# MotherBoard_Interconnect.net
KiCad netlist of a schematic drawn in Altium Designer
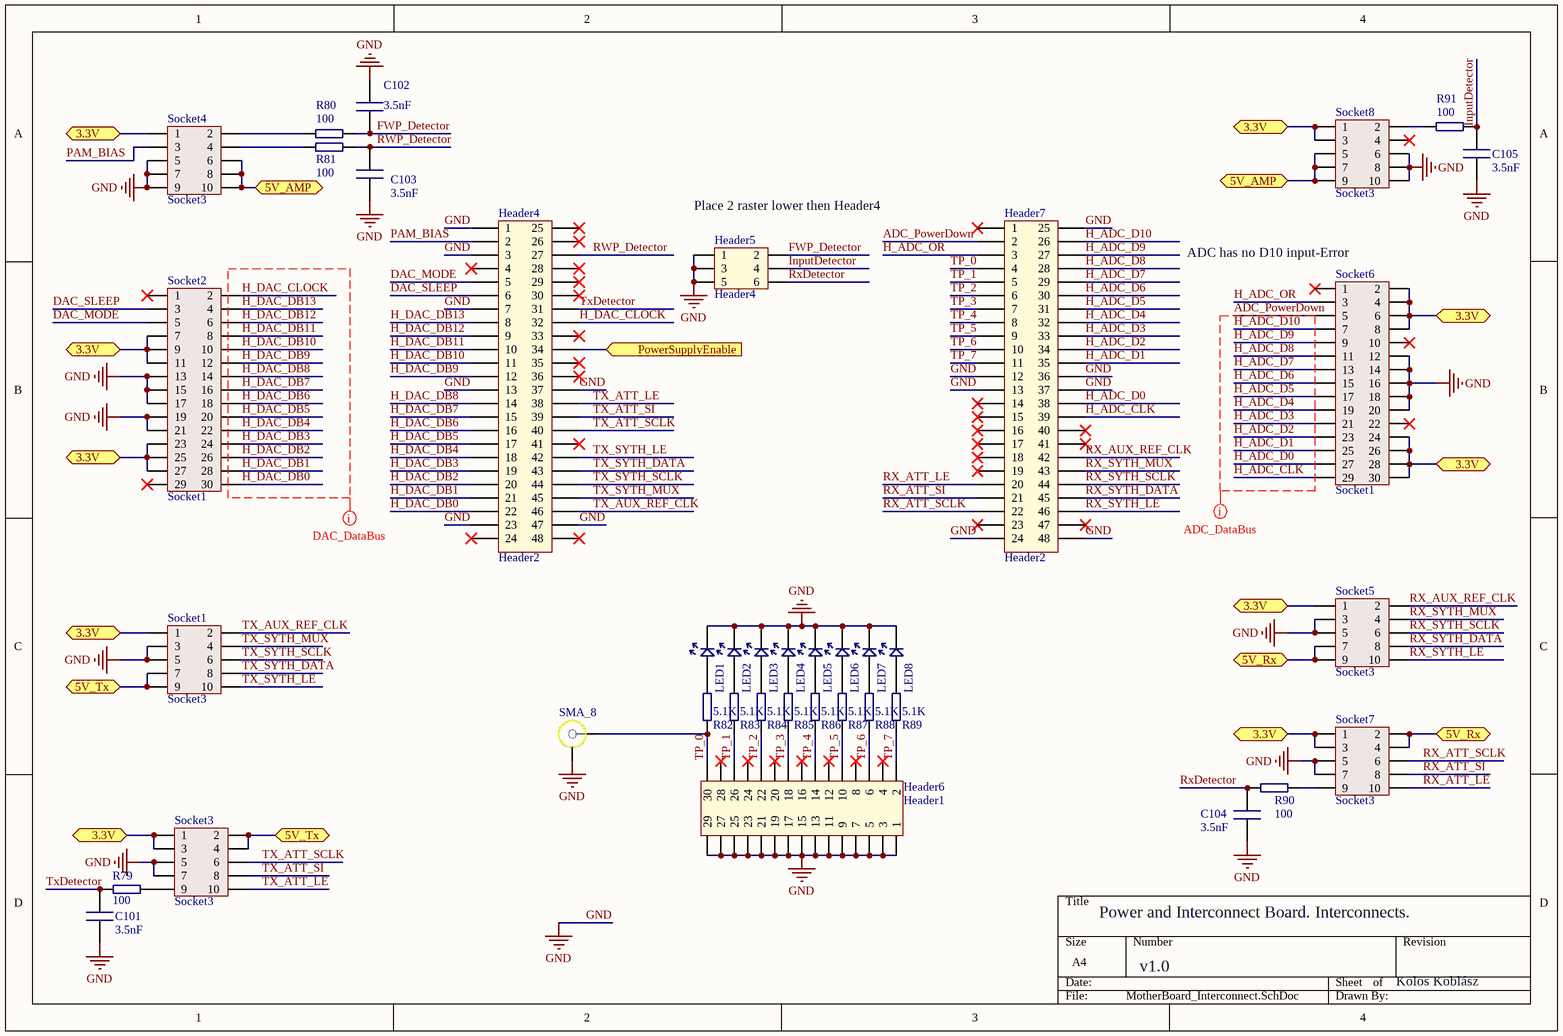
[diagram p0: MotherBoard_Interconnect.SchDoc]

(export (version "E")
  (design (tool "Eeschema 10.0.6"))
  (components
    (comp (ref "C101")
      (value "3.5nF")
      (footprint "0805 SMD Passive")
      (description "SMD Capacitor")
      (fields (field (name "Comment") "Cap1"))
      (libsource (lib "RadioProjectSchLib") (part "Cap1"))
    )
    (comp (ref "C102")
      (value "3.5nF")
      (footprint "0805 SMD Passive")
      (description "SMD Capacitor")
      (fields (field (name "Comment") "Cap1"))
      (libsource (lib "RadioProjectSchLib") (part "Cap1"))
    )
    (comp (ref "C103")
      (value "3.5nF")
      (footprint "0805 SMD Passive")
      (description "SMD Capacitor")
      (fields (field (name "Comment") "Cap1"))
      (libsource (lib "RadioProjectSchLib") (part "Cap1"))
    )
    (comp (ref "C104")
      (value "3.5nF")
      (footprint "0805 SMD Passive")
      (description "SMD Capacitor")
      (fields (field (name "Comment") "Cap1"))
      (libsource (lib "RadioProjectSchLib") (part "Cap1"))
    )
    (comp (ref "C105")
      (value "3.5nF")
      (footprint "0805 SMD Passive")
      (description "SMD Capacitor")
      (fields (field (name "Comment") "Cap1"))
      (libsource (lib "RadioProjectSchLib") (part "Cap1"))
    )
    (comp (ref "Header4")
      (value "Header2")
      (footprint "Header2")
      (description "48 Pin Header")
      (libsource (lib "RadioProjectSchLib") (part "Header2"))
    )
    (comp (ref "Header5")
      (value "Header4")
      (footprint "Header4")
      (description "6pin DIL header")
      (libsource (lib "RadioProjectSchLib") (part "Header4"))
    )
    (comp (ref "Header6")
      (value "Header1")
      (footprint "Header1")
      (description "29 Pin Header")
      (fields (field (name "PARTNUMBER") "TLW-115-01-G-D-002-RA"))
      (libsource (lib "RadioProjectSchLib") (part "Header1"))
    )
    (comp (ref "Header7")
      (value "Header2")
      (footprint "Header2")
      (description "48 Pin Header")
      (libsource (lib "RadioProjectSchLib") (part "Header2"))
    )
    (comp (ref "LED1")
      (value "TP0")
      (footprint "0805 SMD Passive")
      (description "Diode")
      (fields (field (name "MANUFACTURER") "LITEON") (field (name "PARTNUMBER") "LTST-C171KGKT"))
      (libsource (lib "RadioProjectSchLib") (part "LED_Green"))
    )
    (comp (ref "LED2")
      (value "TP1")
      (footprint "0805 SMD Passive")
      (description "Diode")
      (fields (field (name "MANUFACTURER") "LITEON") (field (name "PARTNUMBER") "LTST-C171KGKT"))
      (libsource (lib "RadioProjectSchLib") (part "LED_Green"))
    )
    (comp (ref "LED3")
      (value "TP2")
      (footprint "0805 SMD Passive")
      (description "Diode")
      (fields (field (name "MANUFACTURER") "LITEON") (field (name "PARTNUMBER") "LTST-C171KGKT"))
      (libsource (lib "RadioProjectSchLib") (part "LED_Green"))
    )
    (comp (ref "LED4")
      (value "TP3")
      (footprint "0805 SMD Passive")
      (description "Diode")
      (fields (field (name "MANUFACTURER") "LITEON") (field (name "PARTNUMBER") "LTST-C171KGKT"))
      (libsource (lib "RadioProjectSchLib") (part "LED_Green"))
    )
    (comp (ref "LED5")
      (value "TP4")
      (footprint "0805 SMD Passive")
      (description "Diode")
      (fields (field (name "MANUFACTURER") "LITEON") (field (name "PARTNUMBER") "LTST-C171KGKT"))
      (libsource (lib "RadioProjectSchLib") (part "LED_Green"))
    )
    (comp (ref "LED6")
      (value "TP5")
      (footprint "0805 SMD Passive")
      (description "Diode")
      (fields (field (name "MANUFACTURER") "LITEON") (field (name "PARTNUMBER") "LTST-C171KGKT"))
      (libsource (lib "RadioProjectSchLib") (part "LED_Green"))
    )
    (comp (ref "LED7")
      (value "TP6")
      (footprint "0805 SMD Passive")
      (description "Diode")
      (fields (field (name "MANUFACTURER") "LITEON") (field (name "PARTNUMBER") "LTST-C171KGKT"))
      (libsource (lib "RadioProjectSchLib") (part "LED_Green"))
    )
    (comp (ref "LED8")
      (value "TP7")
      (footprint "0805 SMD Passive")
      (description "Diode")
      (fields (field (name "MANUFACTURER") "LITEON") (field (name "PARTNUMBER") "LTST-C171KGKT"))
      (libsource (lib "RadioProjectSchLib") (part "LED_Green"))
    )
    (comp (ref "R79")
      (value "100")
      (footprint "0805 SMD Passive")
      (description "SMD Resistor")
      (fields (field (name "Comment") "Resistor"))
      (libsource (lib "RadioProjectSchLib") (part "Res1"))
    )
    (comp (ref "R80")
      (value "100")
      (footprint "0805 SMD Passive")
      (description "SMD Resistor")
      (fields (field (name "Comment") "Resistor"))
      (libsource (lib "RadioProjectSchLib") (part "Res1"))
    )
    (comp (ref "R81")
      (value "100")
      (footprint "0805 SMD Passive")
      (description "SMD Resistor")
      (fields (field (name "Comment") "Resistor"))
      (libsource (lib "RadioProjectSchLib") (part "Res1"))
    )
    (comp (ref "R82")
      (value "5.1K")
      (footprint "0805 SMD Passive")
      (description "SMD Resistor")
      (fields (field (name "Comment") "Resistor"))
      (libsource (lib "RadioProjectSchLib") (part "Res1"))
    )
    (comp (ref "R83")
      (value "5.1K")
      (footprint "0805 SMD Passive")
      (description "SMD Resistor")
      (fields (field (name "Comment") "Resistor"))
      (libsource (lib "RadioProjectSchLib") (part "Res1"))
    )
    (comp (ref "R84")
      (value "5.1K")
      (footprint "0805 SMD Passive")
      (description "SMD Resistor")
      (fields (field (name "Comment") "Resistor"))
      (libsource (lib "RadioProjectSchLib") (part "Res1"))
    )
    (comp (ref "R85")
      (value "5.1K")
      (footprint "0805 SMD Passive")
      (description "SMD Resistor")
      (fields (field (name "Comment") "Resistor"))
      (libsource (lib "RadioProjectSchLib") (part "Res1"))
    )
    (comp (ref "R86")
      (value "5.1K")
      (footprint "0805 SMD Passive")
      (description "SMD Resistor")
      (fields (field (name "Comment") "Resistor"))
      (libsource (lib "RadioProjectSchLib") (part "Res1"))
    )
    (comp (ref "R87")
      (value "5.1K")
      (footprint "0805 SMD Passive")
      (description "SMD Resistor")
      (fields (field (name "Comment") "Resistor"))
      (libsource (lib "RadioProjectSchLib") (part "Res1"))
    )
    (comp (ref "R88")
      (value "5.1K")
      (footprint "0805 SMD Passive")
      (description "SMD Resistor")
      (fields (field (name "Comment") "Resistor"))
      (libsource (lib "RadioProjectSchLib") (part "Res1"))
    )
    (comp (ref "R89")
      (value "5.1K")
      (footprint "0805 SMD Passive")
      (description "SMD Resistor")
      (fields (field (name "Comment") "Resistor"))
      (libsource (lib "RadioProjectSchLib") (part "Res1"))
    )
    (comp (ref "R90")
      (value "100")
      (footprint "0805 SMD Passive")
      (description "SMD Resistor")
      (fields (field (name "Comment") "Resistor"))
      (libsource (lib "RadioProjectSchLib") (part "Res1"))
    )
    (comp (ref "R91")
      (value "100")
      (footprint "0805 SMD Passive")
      (description "SMD Resistor")
      (fields (field (name "Comment") "Resistor"))
      (libsource (lib "RadioProjectSchLib") (part "Res1"))
    )
    (comp (ref "SMA_8")
      (value "SMA_2")
      (footprint "SMA_Board")
      (description "SMA Female")
      (libsource (lib "RadioProjectSchLib") (part "SMA_2"))
    )
    (comp (ref "Socket1")
      (value "Socket3")
      (footprint "Socket3")
      (description "10 Pin Socket")
      (libsource (lib "RadioProjectSchLib") (part "Socket3"))
    )
    (comp (ref "Socket2")
      (value "Socket1")
      (footprint "Socket1")
      (description "30 Pin Socket")
      (fields (field (name "PARTNUMBER") "SLW-115-01-G-D"))
      (libsource (lib "RadioProjectSchLib") (part "Socket1"))
    )
    (comp (ref "Socket3")
      (value "Socket3")
      (footprint "Socket3")
      (description "10 Pin Socket")
      (libsource (lib "RadioProjectSchLib") (part "Socket3"))
    )
    (comp (ref "Socket4")
      (value "Socket3")
      (footprint "Socket3")
      (description "10 Pin Socket")
      (libsource (lib "RadioProjectSchLib") (part "Socket3"))
    )
    (comp (ref "Socket5")
      (value "Socket3")
      (footprint "Socket3")
      (description "10 Pin Socket")
      (libsource (lib "RadioProjectSchLib") (part "Socket3"))
    )
    (comp (ref "Socket6")
      (value "Socket1")
      (footprint "Socket1")
      (description "30 Pin Socket")
      (fields (field (name "PARTNUMBER") "SLW-115-01-G-D"))
      (libsource (lib "RadioProjectSchLib") (part "Socket1"))
    )
    (comp (ref "Socket7")
      (value "Socket3")
      (footprint "Socket3")
      (description "10 Pin Socket")
      (libsource (lib "RadioProjectSchLib") (part "Socket3"))
    )
    (comp (ref "Socket8")
      (value "Socket3")
      (footprint "Socket3")
      (description "10 Pin Socket")
      (libsource (lib "RadioProjectSchLib") (part "Socket3"))
    )
  )
  (nets
    (net (code "1") (name "/3.3V") (class "Default")
      (node (ref "Socket1") (pin "1") (pinfunction "1_1") (pintype "passive"))
      (node (ref "Socket2") (pin "11") (pinfunction "11_11") (pintype "passive"))
      (node (ref "Socket2") (pin "23") (pinfunction "23_23") (pintype "passive"))
      (node (ref "Socket2") (pin "25") (pinfunction "25_25") (pintype "passive"))
      (node (ref "Socket2") (pin "27") (pinfunction "27_27") (pintype "passive"))
      (node (ref "Socket2") (pin "7") (pinfunction "7_7") (pintype "passive"))
      (node (ref "Socket2") (pin "9") (pinfunction "9_9") (pintype "passive"))
      (node (ref "Socket3") (pin "1") (pinfunction "1_1") (pintype "passive"))
      (node (ref "Socket3") (pin "3") (pinfunction "3_3") (pintype "passive"))
      (node (ref "Socket4") (pin "1") (pinfunction "1_1") (pintype "passive"))
      (node (ref "Socket5") (pin "1") (pinfunction "1_1") (pintype "passive"))
      (node (ref "Socket6") (pin "2") (pinfunction "2_2") (pintype "passive"))
      (node (ref "Socket6") (pin "24") (pinfunction "24_24") (pintype "passive"))
      (node (ref "Socket6") (pin "26") (pinfunction "26_26") (pintype "passive"))
      (node (ref "Socket6") (pin "28") (pinfunction "28_28") (pintype "passive"))
      (node (ref "Socket6") (pin "30") (pinfunction "30_30") (pintype "passive"))
      (node (ref "Socket6") (pin "4") (pinfunction "4_4") (pintype "passive"))
      (node (ref "Socket6") (pin "6") (pinfunction "6_6") (pintype "passive"))
      (node (ref "Socket6") (pin "8") (pinfunction "8_8") (pintype "passive"))
      (node (ref "Socket7") (pin "1") (pinfunction "1_1") (pintype "passive"))
      (node (ref "Socket7") (pin "3") (pinfunction "3_3") (pintype "passive"))
      (node (ref "Socket8") (pin "1") (pinfunction "1_1") (pintype "passive"))
      (node (ref "Socket8") (pin "3") (pinfunction "3_3") (pintype "passive"))
    )
    (net (code "2") (name "/5V_AMP") (class "Default")
      (node (ref "Socket4") (pin "10") (pinfunction "10_10") (pintype "passive"))
      (node (ref "Socket4") (pin "6") (pinfunction "6_6") (pintype "passive"))
      (node (ref "Socket4") (pin "8") (pinfunction "8_8") (pintype "passive"))
      (node (ref "Socket8") (pin "5") (pinfunction "5_5") (pintype "passive"))
      (node (ref "Socket8") (pin "7") (pinfunction "7_7") (pintype "passive"))
      (node (ref "Socket8") (pin "9") (pinfunction "9_9") (pintype "passive"))
    )
    (net (code "3") (name "/5V_Rx") (class "Default")
      (node (ref "Socket5") (pin "7") (pinfunction "7_7") (pintype "passive"))
      (node (ref "Socket5") (pin "9") (pinfunction "9_9") (pintype "passive"))
      (node (ref "Socket7") (pin "2") (pinfunction "2_2") (pintype "passive"))
      (node (ref "Socket7") (pin "4") (pinfunction "4_4") (pintype "passive"))
    )
    (net (code "4") (name "/5V_Tx") (class "Default")
      (node (ref "Socket1") (pin "7") (pinfunction "7_7") (pintype "passive"))
      (node (ref "Socket1") (pin "9") (pinfunction "9_9") (pintype "passive"))
      (node (ref "Socket3") (pin "2") (pinfunction "2_2") (pintype "passive"))
      (node (ref "Socket3") (pin "4") (pinfunction "4_4") (pintype "passive"))
    )
    (net (code "5") (name "/ADC_PowerDown") (class "Default")
      (node (ref "Header7") (pin "2") (pinfunction "2_2") (pintype "passive"))
      (node (ref "Socket6") (pin "5") (pinfunction "5_5") (pintype "passive"))
    )
    (net (code "6") (name "/DAC_MODE") (class "Default")
      (node (ref "Header4") (pin "5") (pinfunction "5_5") (pintype "passive"))
      (node (ref "Socket2") (pin "5") (pinfunction "5_5") (pintype "passive"))
    )
    (net (code "7") (name "/DAC_SLEEP") (class "Default")
      (node (ref "Header4") (pin "6") (pinfunction "6_6") (pintype "passive"))
      (node (ref "Socket2") (pin "3") (pinfunction "3_3") (pintype "passive"))
    )
    (net (code "8") (name "/FWP_Detector") (class "Default")
      (node (ref "C102") (pin "1") (pinfunction "*_1") (pintype "passive"))
      (node (ref "Header5") (pin "2") (pinfunction "2_2") (pintype "passive"))
      (node (ref "R80") (pin "2") (pinfunction "*_2") (pintype "passive"))
    )
    (net (code "9") (name "/H_ADC_CLK") (class "Default")
      (node (ref "Header7") (pin "39") (pinfunction "39_39") (pintype "passive"))
      (node (ref "Socket6") (pin "29") (pinfunction "29_29") (pintype "passive"))
    )
    (net (code "10") (name "/H_ADC_D0") (class "Default")
      (node (ref "Header7") (pin "38") (pinfunction "38_38") (pintype "passive"))
      (node (ref "Socket6") (pin "27") (pinfunction "27_27") (pintype "passive"))
    )
    (net (code "11") (name "/H_ADC_D1") (class "Default")
      (node (ref "Header7") (pin "35") (pinfunction "35_35") (pintype "passive"))
      (node (ref "Socket6") (pin "25") (pinfunction "25_25") (pintype "passive"))
    )
    (net (code "12") (name "/H_ADC_D2") (class "Default")
      (node (ref "Header7") (pin "34") (pinfunction "34_34") (pintype "passive"))
      (node (ref "Socket6") (pin "23") (pinfunction "23_23") (pintype "passive"))
    )
    (net (code "13") (name "/H_ADC_D3") (class "Default")
      (node (ref "Header7") (pin "33") (pinfunction "33_33") (pintype "passive"))
      (node (ref "Socket6") (pin "21") (pinfunction "21_21") (pintype "passive"))
    )
    (net (code "14") (name "/H_ADC_D4") (class "Default")
      (node (ref "Header7") (pin "32") (pinfunction "32_32") (pintype "passive"))
      (node (ref "Socket6") (pin "19") (pinfunction "19_19") (pintype "passive"))
    )
    (net (code "15") (name "/H_ADC_D5") (class "Default")
      (node (ref "Header7") (pin "31") (pinfunction "31_31") (pintype "passive"))
      (node (ref "Socket6") (pin "17") (pinfunction "17_17") (pintype "passive"))
    )
    (net (code "16") (name "/H_ADC_D6") (class "Default")
      (node (ref "Header7") (pin "30") (pinfunction "30_30") (pintype "passive"))
      (node (ref "Socket6") (pin "15") (pinfunction "15_15") (pintype "passive"))
    )
    (net (code "17") (name "/H_ADC_D7") (class "Default")
      (node (ref "Header7") (pin "29") (pinfunction "29_29") (pintype "passive"))
      (node (ref "Socket6") (pin "13") (pinfunction "13_13") (pintype "passive"))
    )
    (net (code "18") (name "/H_ADC_D8") (class "Default")
      (node (ref "Header7") (pin "28") (pinfunction "28_28") (pintype "passive"))
      (node (ref "Socket6") (pin "11") (pinfunction "11_11") (pintype "passive"))
    )
    (net (code "19") (name "/H_ADC_D9") (class "Default")
      (node (ref "Header7") (pin "27") (pinfunction "27_27") (pintype "passive"))
      (node (ref "Socket6") (pin "9") (pinfunction "9_9") (pintype "passive"))
    )
    (net (code "20") (name "/H_ADC_D10") (class "Default")
      (node (ref "Header7") (pin "26") (pinfunction "26_26") (pintype "passive"))
      (node (ref "Socket6") (pin "7") (pinfunction "7_7") (pintype "passive"))
    )
    (net (code "21") (name "/H_ADC_OR") (class "Default")
      (node (ref "Header7") (pin "3") (pinfunction "3_3") (pintype "passive"))
      (node (ref "Socket6") (pin "3") (pinfunction "3_3") (pintype "passive"))
    )
    (net (code "22") (name "/H_DAC_CLOCK") (class "Default")
      (node (ref "Header4") (pin "32") (pinfunction "32_32") (pintype "passive"))
      (node (ref "Socket2") (pin "2") (pinfunction "2_2") (pintype "passive"))
    )
    (net (code "23") (name "/H_DAC_DB0") (class "Default")
      (node (ref "Header4") (pin "22") (pinfunction "22_22") (pintype "passive"))
      (node (ref "Socket2") (pin "30") (pinfunction "30_30") (pintype "passive"))
    )
    (net (code "24") (name "/H_DAC_DB1") (class "Default")
      (node (ref "Header4") (pin "21") (pinfunction "21_21") (pintype "passive"))
      (node (ref "Socket2") (pin "28") (pinfunction "28_28") (pintype "passive"))
    )
    (net (code "25") (name "/H_DAC_DB2") (class "Default")
      (node (ref "Header4") (pin "20") (pinfunction "20_20") (pintype "passive"))
      (node (ref "Socket2") (pin "26") (pinfunction "26_26") (pintype "passive"))
    )
    (net (code "26") (name "/H_DAC_DB3") (class "Default")
      (node (ref "Header4") (pin "19") (pinfunction "19_19") (pintype "passive"))
      (node (ref "Socket2") (pin "24") (pinfunction "24_24") (pintype "passive"))
    )
    (net (code "27") (name "/H_DAC_DB4") (class "Default")
      (node (ref "Header4") (pin "18") (pinfunction "18_18") (pintype "passive"))
      (node (ref "Socket2") (pin "22") (pinfunction "22_22") (pintype "passive"))
    )
    (net (code "28") (name "/H_DAC_DB5") (class "Default")
      (node (ref "Header4") (pin "17") (pinfunction "17_17") (pintype "passive"))
      (node (ref "Socket2") (pin "20") (pinfunction "20_20") (pintype "passive"))
    )
    (net (code "29") (name "/H_DAC_DB6") (class "Default")
      (node (ref "Header4") (pin "16") (pinfunction "16_16") (pintype "passive"))
      (node (ref "Socket2") (pin "18") (pinfunction "18_18") (pintype "passive"))
    )
    (net (code "30") (name "/H_DAC_DB7") (class "Default")
      (node (ref "Header4") (pin "15") (pinfunction "15_15") (pintype "passive"))
      (node (ref "Socket2") (pin "16") (pinfunction "16_16") (pintype "passive"))
    )
    (net (code "31") (name "/H_DAC_DB8") (class "Default")
      (node (ref "Header4") (pin "14") (pinfunction "14_14") (pintype "passive"))
      (node (ref "Socket2") (pin "14") (pinfunction "14_14") (pintype "passive"))
    )
    (net (code "32") (name "/H_DAC_DB9") (class "Default")
      (node (ref "Header4") (pin "12") (pinfunction "12_12") (pintype "passive"))
      (node (ref "Socket2") (pin "12") (pinfunction "12_12") (pintype "passive"))
    )
    (net (code "33") (name "/H_DAC_DB10") (class "Default")
      (node (ref "Header4") (pin "11") (pinfunction "11_11") (pintype "passive"))
      (node (ref "Socket2") (pin "10") (pinfunction "10_10") (pintype "passive"))
    )
    (net (code "34") (name "/H_DAC_DB11") (class "Default")
      (node (ref "Header4") (pin "10") (pinfunction "10_10") (pintype "passive"))
      (node (ref "Socket2") (pin "8") (pinfunction "8_8") (pintype "passive"))
    )
    (net (code "35") (name "/H_DAC_DB12") (class "Default")
      (node (ref "Header4") (pin "9") (pinfunction "9_9") (pintype "passive"))
      (node (ref "Socket2") (pin "6") (pinfunction "6_6") (pintype "passive"))
    )
    (net (code "36") (name "/H_DAC_DB13") (class "Default")
      (node (ref "Header4") (pin "8") (pinfunction "8_8") (pintype "passive"))
      (node (ref "Socket2") (pin "4") (pinfunction "4_4") (pintype "passive"))
    )
    (net (code "37") (name "/InputDetector") (class "Default")
      (node (ref "C105") (pin "1") (pinfunction "*_1") (pintype "passive"))
      (node (ref "Header5") (pin "4") (pinfunction "4_4") (pintype "passive"))
      (node (ref "R91") (pin "1") (pinfunction "*_1") (pintype "passive"))
    )
    (net (code "38") (name "/PAM_BIAS") (class "Default")
      (node (ref "Header4") (pin "2") (pinfunction "2_2") (pintype "passive"))
      (node (ref "Socket4") (pin "3") (pinfunction "3_3") (pintype "passive"))
    )
    (net (code "39") (name "/PowerSupplyEnable") (class "Default")
      (node (ref "Header4") (pin "34") (pinfunction "34_34") (pintype "passive"))
    )
    (net (code "40") (name "/RWP_Detector") (class "Default")
      (node (ref "C103") (pin "1") (pinfunction "*_1") (pintype "passive"))
      (node (ref "Header4") (pin "27") (pinfunction "27_27") (pintype "passive"))
      (node (ref "R81") (pin "2") (pinfunction "*_2") (pintype "passive"))
    )
    (net (code "41") (name "/RX_ATT_LE") (class "Default")
      (node (ref "Header7") (pin "20") (pinfunction "20_20") (pintype "passive"))
      (node (ref "Socket7") (pin "10") (pinfunction "10_10") (pintype "passive"))
    )
    (net (code "42") (name "/RX_ATT_SCLK") (class "Default")
      (node (ref "Header7") (pin "22") (pinfunction "22_22") (pintype "passive"))
      (node (ref "Socket7") (pin "6") (pinfunction "6_6") (pintype "passive"))
    )
    (net (code "43") (name "/RX_ATT_SI") (class "Default")
      (node (ref "Header7") (pin "21") (pinfunction "21_21") (pintype "passive"))
      (node (ref "Socket7") (pin "8") (pinfunction "8_8") (pintype "passive"))
    )
    (net (code "44") (name "/RX_AUX_REF_CLK") (class "Default")
      (node (ref "Header7") (pin "42") (pinfunction "42_42") (pintype "passive"))
      (node (ref "Socket5") (pin "2") (pinfunction "2_2") (pintype "passive"))
    )
    (net (code "45") (name "/RX_SYTH_DATA") (class "Default")
      (node (ref "Header7") (pin "45") (pinfunction "45_45") (pintype "passive"))
      (node (ref "Socket5") (pin "8") (pinfunction "8_8") (pintype "passive"))
    )
    (net (code "46") (name "/RX_SYTH_LE") (class "Default")
      (node (ref "Header7") (pin "46") (pinfunction "46_46") (pintype "passive"))
      (node (ref "Socket5") (pin "10") (pinfunction "10_10") (pintype "passive"))
    )
    (net (code "47") (name "/RX_SYTH_MUX") (class "Default")
      (node (ref "Header7") (pin "43") (pinfunction "43_43") (pintype "passive"))
      (node (ref "Socket5") (pin "4") (pinfunction "4_4") (pintype "passive"))
    )
    (net (code "48") (name "/RX_SYTH_SCLK") (class "Default")
      (node (ref "Header7") (pin "44") (pinfunction "44_44") (pintype "passive"))
      (node (ref "Socket5") (pin "6") (pinfunction "6_6") (pintype "passive"))
    )
    (net (code "49") (name "/RxDetector") (class "Default")
      (node (ref "C104") (pin "1") (pinfunction "*_1") (pintype "passive"))
      (node (ref "Header5") (pin "6") (pinfunction "6_6") (pintype "passive"))
      (node (ref "R90") (pin "1") (pinfunction "*_1") (pintype "passive"))
    )
    (net (code "50") (name "/TP_0") (class "Default")
      (node (ref "Header6") (pin "30") (pinfunction "30_30") (pintype "passive"))
      (node (ref "Header7") (pin "4") (pinfunction "4_4") (pintype "passive"))
      (node (ref "R82") (pin "1") (pinfunction "*_1") (pintype "passive"))
      (node (ref "SMA_8") (pin "1") (pinfunction "1_1") (pintype "passive"))
    )
    (net (code "51") (name "/TP_1") (class "Default")
      (node (ref "Header6") (pin "26") (pinfunction "26_26") (pintype "passive"))
      (node (ref "Header7") (pin "5") (pinfunction "5_5") (pintype "passive"))
      (node (ref "R83") (pin "1") (pinfunction "*_1") (pintype "passive"))
    )
    (net (code "52") (name "/TP_2") (class "Default")
      (node (ref "Header6") (pin "22") (pinfunction "22_22") (pintype "passive"))
      (node (ref "Header7") (pin "6") (pinfunction "6_6") (pintype "passive"))
      (node (ref "R84") (pin "1") (pinfunction "*_1") (pintype "passive"))
    )
    (net (code "53") (name "/TP_3") (class "Default")
      (node (ref "Header6") (pin "18") (pinfunction "18_18") (pintype "passive"))
      (node (ref "Header7") (pin "7") (pinfunction "7_7") (pintype "passive"))
      (node (ref "R85") (pin "1") (pinfunction "*_1") (pintype "passive"))
    )
    (net (code "54") (name "/TP_4") (class "Default")
      (node (ref "Header6") (pin "14") (pinfunction "14_14") (pintype "passive"))
      (node (ref "Header7") (pin "8") (pinfunction "8_8") (pintype "passive"))
      (node (ref "R86") (pin "1") (pinfunction "*_1") (pintype "passive"))
    )
    (net (code "55") (name "/TP_5") (class "Default")
      (node (ref "Header6") (pin "10") (pinfunction "10_10") (pintype "passive"))
      (node (ref "Header7") (pin "9") (pinfunction "9_9") (pintype "passive"))
      (node (ref "R87") (pin "1") (pinfunction "*_1") (pintype "passive"))
    )
    (net (code "56") (name "/TP_6") (class "Default")
      (node (ref "Header6") (pin "6") (pinfunction "6_6") (pintype "passive"))
      (node (ref "Header7") (pin "10") (pinfunction "10_10") (pintype "passive"))
      (node (ref "R88") (pin "1") (pinfunction "*_1") (pintype "passive"))
    )
    (net (code "57") (name "/TP_7") (class "Default")
      (node (ref "Header6") (pin "2") (pinfunction "2_2") (pintype "passive"))
      (node (ref "Header7") (pin "11") (pinfunction "11_11") (pintype "passive"))
      (node (ref "R89") (pin "1") (pinfunction "*_1") (pintype "passive"))
    )
    (net (code "58") (name "/TX_ATT_LE") (class "Default")
      (node (ref "Header4") (pin "38") (pinfunction "38_38") (pintype "passive"))
      (node (ref "Socket3") (pin "10") (pinfunction "10_10") (pintype "passive"))
    )
    (net (code "59") (name "/TX_ATT_SCLK") (class "Default")
      (node (ref "Header4") (pin "40") (pinfunction "40_40") (pintype "passive"))
      (node (ref "Socket3") (pin "6") (pinfunction "6_6") (pintype "passive"))
    )
    (net (code "60") (name "/TX_ATT_SI") (class "Default")
      (node (ref "Header4") (pin "39") (pinfunction "39_39") (pintype "passive"))
      (node (ref "Socket3") (pin "8") (pinfunction "8_8") (pintype "passive"))
    )
    (net (code "61") (name "/TX_AUX_REF_CLK") (class "Default")
      (node (ref "Header4") (pin "46") (pinfunction "46_46") (pintype "passive"))
      (node (ref "Socket1") (pin "2") (pinfunction "2_2") (pintype "passive"))
    )
    (net (code "62") (name "/TX_SYTH_DATA") (class "Default")
      (node (ref "Header4") (pin "43") (pinfunction "43_43") (pintype "passive"))
      (node (ref "Socket1") (pin "8") (pinfunction "8_8") (pintype "passive"))
    )
    (net (code "63") (name "/TX_SYTH_LE") (class "Default")
      (node (ref "Header4") (pin "42") (pinfunction "42_42") (pintype "passive"))
      (node (ref "Socket1") (pin "10") (pinfunction "10_10") (pintype "passive"))
    )
    (net (code "64") (name "/TX_SYTH_MUX") (class "Default")
      (node (ref "Header4") (pin "45") (pinfunction "45_45") (pintype "passive"))
      (node (ref "Socket1") (pin "4") (pinfunction "4_4") (pintype "passive"))
    )
    (net (code "65") (name "/TX_SYTH_SCLK") (class "Default")
      (node (ref "Header4") (pin "44") (pinfunction "44_44") (pintype "passive"))
      (node (ref "Socket1") (pin "6") (pinfunction "6_6") (pintype "passive"))
    )
    (net (code "66") (name "/TxDetector") (class "Default")
      (node (ref "C101") (pin "1") (pinfunction "*_1") (pintype "passive"))
      (node (ref "Header4") (pin "31") (pinfunction "31_31") (pintype "passive"))
      (node (ref "R79") (pin "1") (pinfunction "*_1") (pintype "passive"))
    )
    (net (code "67") (name "GND") (class "Default")
      (node (ref "C101") (pin "2") (pinfunction "*_2") (pintype "passive"))
      (node (ref "C102") (pin "2") (pinfunction "*_2") (pintype "passive"))
      (node (ref "C103") (pin "2") (pinfunction "*_2") (pintype "passive"))
      (node (ref "C104") (pin "2") (pinfunction "*_2") (pintype "passive"))
      (node (ref "C105") (pin "2") (pinfunction "*_2") (pintype "passive"))
      (node (ref "Header4") (pin "1") (pinfunction "1_1") (pintype "passive"))
      (node (ref "Header4") (pin "13") (pinfunction "13_13") (pintype "passive"))
      (node (ref "Header4") (pin "23") (pinfunction "23_23") (pintype "passive"))
      (node (ref "Header4") (pin "3") (pinfunction "3_3") (pintype "passive"))
      (node (ref "Header4") (pin "37") (pinfunction "37_37") (pintype "passive"))
      (node (ref "Header4") (pin "47") (pinfunction "47_47") (pintype "passive"))
      (node (ref "Header4") (pin "7") (pinfunction "7_7") (pintype "passive"))
      (node (ref "Header5") (pin "1") (pinfunction "1_1") (pintype "passive"))
      (node (ref "Header5") (pin "3") (pinfunction "3_3") (pintype "passive"))
      (node (ref "Header5") (pin "5") (pinfunction "5_5") (pintype "passive"))
      (node (ref "Header6") (pin "1") (pinfunction "1_1") (pintype "passive"))
      (node (ref "Header6") (pin "11") (pinfunction "11_11") (pintype "passive"))
      (node (ref "Header6") (pin "13") (pinfunction "13_13") (pintype "passive"))
      (node (ref "Header6") (pin "15") (pinfunction "15_15") (pintype "passive"))
      (node (ref "Header6") (pin "17") (pinfunction "17_17") (pintype "passive"))
      (node (ref "Header6") (pin "19") (pinfunction "19_19") (pintype "passive"))
      (node (ref "Header6") (pin "21") (pinfunction "21_21") (pintype "passive"))
      (node (ref "Header6") (pin "23") (pinfunction "23_23") (pintype "passive"))
      (node (ref "Header6") (pin "25") (pinfunction "25_25") (pintype "passive"))
      (node (ref "Header6") (pin "27") (pinfunction "27_27") (pintype "passive"))
      (node (ref "Header6") (pin "29") (pinfunction "29_29") (pintype "passive"))
      (node (ref "Header6") (pin "3") (pinfunction "3_3") (pintype "passive"))
      (node (ref "Header6") (pin "5") (pinfunction "5_5") (pintype "passive"))
      (node (ref "Header6") (pin "7") (pinfunction "7_7") (pintype "passive"))
      (node (ref "Header6") (pin "9") (pinfunction "9_9") (pintype "passive"))
      (node (ref "Header7") (pin "12") (pinfunction "12_12") (pintype "passive"))
      (node (ref "Header7") (pin "13") (pinfunction "13_13") (pintype "passive"))
      (node (ref "Header7") (pin "24") (pinfunction "24_24") (pintype "passive"))
      (node (ref "Header7") (pin "25") (pinfunction "25_25") (pintype "passive"))
      (node (ref "Header7") (pin "36") (pinfunction "36_36") (pintype "passive"))
      (node (ref "Header7") (pin "37") (pinfunction "37_37") (pintype "passive"))
      (node (ref "Header7") (pin "48") (pinfunction "48_48") (pintype "passive"))
      (node (ref "LED1") (pin "1") (pinfunction "K_1") (pintype "passive"))
      (node (ref "LED2") (pin "1") (pinfunction "K_1") (pintype "passive"))
      (node (ref "LED3") (pin "1") (pinfunction "K_1") (pintype "passive"))
      (node (ref "LED4") (pin "1") (pinfunction "K_1") (pintype "passive"))
      (node (ref "LED5") (pin "1") (pinfunction "K_1") (pintype "passive"))
      (node (ref "LED6") (pin "1") (pinfunction "K_1") (pintype "passive"))
      (node (ref "LED7") (pin "1") (pinfunction "K_1") (pintype "passive"))
      (node (ref "LED8") (pin "1") (pinfunction "K_1") (pintype "passive"))
      (node (ref "SMA_8") (pin "2") (pinfunction "2_2") (pintype "passive"))
      (node (ref "Socket1") (pin "3") (pinfunction "3_3") (pintype "passive"))
      (node (ref "Socket1") (pin "5") (pinfunction "5_5") (pintype "passive"))
      (node (ref "Socket2") (pin "13") (pinfunction "13_13") (pintype "passive"))
      (node (ref "Socket2") (pin "15") (pinfunction "15_15") (pintype "passive"))
      (node (ref "Socket2") (pin "17") (pinfunction "17_17") (pintype "passive"))
      (node (ref "Socket2") (pin "19") (pinfunction "19_19") (pintype "passive"))
      (node (ref "Socket2") (pin "21") (pinfunction "21_21") (pintype "passive"))
      (node (ref "Socket3") (pin "5") (pinfunction "5_5") (pintype "passive"))
      (node (ref "Socket3") (pin "7") (pinfunction "7_7") (pintype "passive"))
      (node (ref "Socket4") (pin "5") (pinfunction "5_5") (pintype "passive"))
      (node (ref "Socket4") (pin "7") (pinfunction "7_7") (pintype "passive"))
      (node (ref "Socket4") (pin "9") (pinfunction "9_9") (pintype "passive"))
      (node (ref "Socket5") (pin "3") (pinfunction "3_3") (pintype "passive"))
      (node (ref "Socket5") (pin "5") (pinfunction "5_5") (pintype "passive"))
      (node (ref "Socket6") (pin "12") (pinfunction "12_12") (pintype "passive"))
      (node (ref "Socket6") (pin "14") (pinfunction "14_14") (pintype "passive"))
      (node (ref "Socket6") (pin "16") (pinfunction "16_16") (pintype "passive"))
      (node (ref "Socket6") (pin "18") (pinfunction "18_18") (pintype "passive"))
      (node (ref "Socket6") (pin "20") (pinfunction "20_20") (pintype "passive"))
      (node (ref "Socket7") (pin "5") (pinfunction "5_5") (pintype "passive"))
      (node (ref "Socket7") (pin "7") (pinfunction "7_7") (pintype "passive"))
      (node (ref "Socket8") (pin "10") (pinfunction "10_10") (pintype "passive"))
      (node (ref "Socket8") (pin "6") (pinfunction "6_6") (pintype "passive"))
      (node (ref "Socket8") (pin "8") (pinfunction "8_8") (pintype "passive"))
    )
    (net (code "68") (name "Net-(LED1-A)") (class "Default")
      (node (ref "LED1") (pin "2") (pinfunction "A_2") (pintype "passive"))
      (node (ref "R82") (pin "2") (pinfunction "*_2") (pintype "passive"))
    )
    (net (code "69") (name "Net-(LED2-A)") (class "Default")
      (node (ref "LED2") (pin "2") (pinfunction "A_2") (pintype "passive"))
      (node (ref "R83") (pin "2") (pinfunction "*_2") (pintype "passive"))
    )
    (net (code "70") (name "Net-(LED3-A)") (class "Default")
      (node (ref "LED3") (pin "2") (pinfunction "A_2") (pintype "passive"))
      (node (ref "R84") (pin "2") (pinfunction "*_2") (pintype "passive"))
    )
    (net (code "71") (name "Net-(LED4-A)") (class "Default")
      (node (ref "LED4") (pin "2") (pinfunction "A_2") (pintype "passive"))
      (node (ref "R85") (pin "2") (pinfunction "*_2") (pintype "passive"))
    )
    (net (code "72") (name "Net-(LED5-A)") (class "Default")
      (node (ref "LED5") (pin "2") (pinfunction "A_2") (pintype "passive"))
      (node (ref "R86") (pin "2") (pinfunction "*_2") (pintype "passive"))
    )
    (net (code "73") (name "Net-(LED6-A)") (class "Default")
      (node (ref "LED6") (pin "2") (pinfunction "A_2") (pintype "passive"))
      (node (ref "R87") (pin "2") (pinfunction "*_2") (pintype "passive"))
    )
    (net (code "74") (name "Net-(LED7-A)") (class "Default")
      (node (ref "LED7") (pin "2") (pinfunction "A_2") (pintype "passive"))
      (node (ref "R88") (pin "2") (pinfunction "*_2") (pintype "passive"))
    )
    (net (code "75") (name "Net-(LED8-A)") (class "Default")
      (node (ref "LED8") (pin "2") (pinfunction "A_2") (pintype "passive"))
      (node (ref "R89") (pin "2") (pinfunction "*_2") (pintype "passive"))
    )
    (net (code "76") (name "Net-(R79-*-Pad2)") (class "Default")
      (node (ref "R79") (pin "2") (pinfunction "*_2") (pintype "passive"))
      (node (ref "Socket3") (pin "9") (pinfunction "9_9") (pintype "passive"))
    )
    (net (code "77") (name "Net-(R80-*-Pad1)") (class "Default")
      (node (ref "R80") (pin "1") (pinfunction "*_1") (pintype "passive"))
      (node (ref "Socket4") (pin "2") (pinfunction "2_2") (pintype "passive"))
    )
    (net (code "78") (name "Net-(R81-*-Pad1)") (class "Default")
      (node (ref "R81") (pin "1") (pinfunction "*_1") (pintype "passive"))
      (node (ref "Socket4") (pin "4") (pinfunction "4_4") (pintype "passive"))
    )
    (net (code "79") (name "Net-(R90-*-Pad2)") (class "Default")
      (node (ref "R90") (pin "2") (pinfunction "*_2") (pintype "passive"))
      (node (ref "Socket7") (pin "9") (pinfunction "9_9") (pintype "passive"))
    )
    (net (code "80") (name "Net-(R91-*-Pad2)") (class "Default")
      (node (ref "R91") (pin "2") (pinfunction "*_2") (pintype "passive"))
      (node (ref "Socket8") (pin "2") (pinfunction "2_2") (pintype "passive"))
    )
    (net (code "81") (name "unconnected-(Header4-Pad4)") (class "Default")
      (node (ref "Header4") (pin "4") (pinfunction "4_4") (pintype "passive+no_connect"))
    )
    (net (code "82") (name "unconnected-(Header4-Pad24)") (class "Default")
      (node (ref "Header4") (pin "24") (pinfunction "24_24") (pintype "passive+no_connect"))
    )
    (net (code "83") (name "unconnected-(Header4-Pad25)") (class "Default")
      (node (ref "Header4") (pin "25") (pinfunction "25_25") (pintype "passive+no_connect"))
    )
    (net (code "84") (name "unconnected-(Header4-Pad26)") (class "Default")
      (node (ref "Header4") (pin "26") (pinfunction "26_26") (pintype "passive+no_connect"))
    )
    (net (code "85") (name "unconnected-(Header4-Pad28)") (class "Default")
      (node (ref "Header4") (pin "28") (pinfunction "28_28") (pintype "passive+no_connect"))
    )
    (net (code "86") (name "unconnected-(Header4-Pad29)") (class "Default")
      (node (ref "Header4") (pin "29") (pinfunction "29_29") (pintype "passive+no_connect"))
    )
    (net (code "87") (name "unconnected-(Header4-Pad30)") (class "Default")
      (node (ref "Header4") (pin "30") (pinfunction "30_30") (pintype "passive+no_connect"))
    )
    (net (code "88") (name "unconnected-(Header4-Pad33)") (class "Default")
      (node (ref "Header4") (pin "33") (pinfunction "33_33") (pintype "passive+no_connect"))
    )
    (net (code "89") (name "unconnected-(Header4-Pad35)") (class "Default")
      (node (ref "Header4") (pin "35") (pinfunction "35_35") (pintype "passive+no_connect"))
    )
    (net (code "90") (name "unconnected-(Header4-Pad36)") (class "Default")
      (node (ref "Header4") (pin "36") (pinfunction "36_36") (pintype "passive+no_connect"))
    )
    (net (code "91") (name "unconnected-(Header4-Pad41)") (class "Default")
      (node (ref "Header4") (pin "41") (pinfunction "41_41") (pintype "passive+no_connect"))
    )
    (net (code "92") (name "unconnected-(Header4-Pad48)") (class "Default")
      (node (ref "Header4") (pin "48") (pinfunction "48_48") (pintype "passive+no_connect"))
    )
    (net (code "93") (name "unconnected-(Header6-Pad4)") (class "Default")
      (node (ref "Header6") (pin "4") (pinfunction "4_4") (pintype "passive+no_connect"))
    )
    (net (code "94") (name "unconnected-(Header6-Pad8)") (class "Default")
      (node (ref "Header6") (pin "8") (pinfunction "8_8") (pintype "passive+no_connect"))
    )
    (net (code "95") (name "unconnected-(Header6-Pad12)") (class "Default")
      (node (ref "Header6") (pin "12") (pinfunction "12_12") (pintype "passive+no_connect"))
    )
    (net (code "96") (name "unconnected-(Header6-Pad16)") (class "Default")
      (node (ref "Header6") (pin "16") (pinfunction "16_16") (pintype "passive+no_connect"))
    )
    (net (code "97") (name "unconnected-(Header6-Pad20)") (class "Default")
      (node (ref "Header6") (pin "20") (pinfunction "20_20") (pintype "passive+no_connect"))
    )
    (net (code "98") (name "unconnected-(Header6-Pad24)") (class "Default")
      (node (ref "Header6") (pin "24") (pinfunction "24_24") (pintype "passive+no_connect"))
    )
    (net (code "99") (name "unconnected-(Header6-Pad28)") (class "Default")
      (node (ref "Header6") (pin "28") (pinfunction "28_28") (pintype "passive+no_connect"))
    )
    (net (code "100") (name "unconnected-(Header7-Pad1)") (class "Default")
      (node (ref "Header7") (pin "1") (pinfunction "1_1") (pintype "passive+no_connect"))
    )
    (net (code "101") (name "unconnected-(Header7-Pad14)") (class "Default")
      (node (ref "Header7") (pin "14") (pinfunction "14_14") (pintype "passive+no_connect"))
    )
    (net (code "102") (name "unconnected-(Header7-Pad15)") (class "Default")
      (node (ref "Header7") (pin "15") (pinfunction "15_15") (pintype "passive+no_connect"))
    )
    (net (code "103") (name "unconnected-(Header7-Pad16)") (class "Default")
      (node (ref "Header7") (pin "16") (pinfunction "16_16") (pintype "passive+no_connect"))
    )
    (net (code "104") (name "unconnected-(Header7-Pad17)") (class "Default")
      (node (ref "Header7") (pin "17") (pinfunction "17_17") (pintype "passive+no_connect"))
    )
    (net (code "105") (name "unconnected-(Header7-Pad18)") (class "Default")
      (node (ref "Header7") (pin "18") (pinfunction "18_18") (pintype "passive+no_connect"))
    )
    (net (code "106") (name "unconnected-(Header7-Pad19)") (class "Default")
      (node (ref "Header7") (pin "19") (pinfunction "19_19") (pintype "passive+no_connect"))
    )
    (net (code "107") (name "unconnected-(Header7-Pad23)") (class "Default")
      (node (ref "Header7") (pin "23") (pinfunction "23_23") (pintype "passive+no_connect"))
    )
    (net (code "108") (name "unconnected-(Header7-Pad40)") (class "Default")
      (node (ref "Header7") (pin "40") (pinfunction "40_40") (pintype "passive+no_connect"))
    )
    (net (code "109") (name "unconnected-(Header7-Pad41)") (class "Default")
      (node (ref "Header7") (pin "41") (pinfunction "41_41") (pintype "passive+no_connect"))
    )
    (net (code "110") (name "unconnected-(Header7-Pad47)") (class "Default")
      (node (ref "Header7") (pin "47") (pinfunction "47_47") (pintype "passive+no_connect"))
    )
    (net (code "111") (name "unconnected-(Socket2-Pad1)") (class "Default")
      (node (ref "Socket2") (pin "1") (pinfunction "1_1") (pintype "passive+no_connect"))
    )
    (net (code "112") (name "unconnected-(Socket2-Pad29)") (class "Default")
      (node (ref "Socket2") (pin "29") (pinfunction "29_29") (pintype "passive+no_connect"))
    )
    (net (code "113") (name "unconnected-(Socket6-Pad1)") (class "Default")
      (node (ref "Socket6") (pin "1") (pinfunction "1_1") (pintype "passive+no_connect"))
    )
    (net (code "114") (name "unconnected-(Socket6-Pad10)") (class "Default")
      (node (ref "Socket6") (pin "10") (pinfunction "10_10") (pintype "passive+no_connect"))
    )
    (net (code "115") (name "unconnected-(Socket6-Pad22)") (class "Default")
      (node (ref "Socket6") (pin "22") (pinfunction "22_22") (pintype "passive+no_connect"))
    )
    (net (code "116") (name "unconnected-(Socket8-Pad4)") (class "Default")
      (node (ref "Socket8") (pin "4") (pinfunction "4_4") (pintype "passive+no_connect"))
    )
  )
)
